# M4.net
KiCad netlist of a schematic drawn in Altium Designer
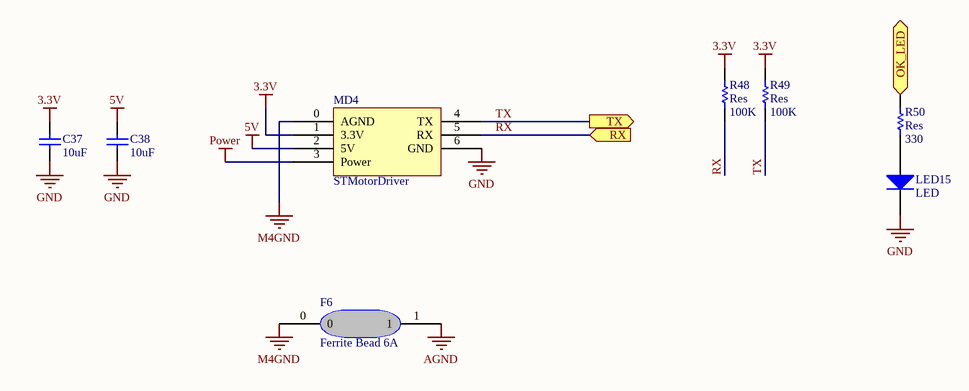
[diagram p0: M4.SchDoc]

(export (version "E")
  (design (tool "Eeschema 10.0.6"))
  (components
    (comp (ref "C37")
      (value "10uF")
      (footprint "2012[0805]")
      (description "Capacitor")
      (fields (field (name "Comment") "Cap_UP") (field (name "PUBLISHER") "Altium Limited"))
      (libsource (lib "KN2CLib") (part "Cap_UP"))
    )
    (comp (ref "C38")
      (value "10uF")
      (footprint "2012[0805]")
      (description "Capacitor")
      (fields (field (name "Comment") "Cap_UP") (field (name "PUBLISHER") "Altium Limited"))
      (libsource (lib "KN2CLib") (part "Cap_UP"))
    )
    (comp (ref "F6")
      (value "Ferrite Bead 6A")
      (footprint "f6A")
      (libsource (lib "Ferrite Bead") (part "F6A"))
    )
    (comp (ref "LED15")
      (value "LED")
      (footprint "2012[0805]")
      (description "1 Amp General Purpose Rectifier")
      (fields (field (name "PUBLISHER") "Altium Limited"))
      (libsource (lib "KN2CLib") (part "Diode"))
    )
    (comp (ref "MD4")
      (value "STMotorDriver")
      (footprint "MotorDriver")
      (libsource (lib "STMotorDriver") (part "STMotorDriver"))
    )
    (comp (ref "R48")
      (value "Res")
      (footprint "2012[0805]")
      (description "Semiconductor Resistor")
      (fields (field (name "ALTIUM_VALUE") "100K") (field (name "PUBLISHER") "Altium Limited"))
      (libsource (lib "KN2CLib") (part "Res"))
    )
    (comp (ref "R49")
      (value "Res")
      (footprint "2012[0805]")
      (description "Semiconductor Resistor")
      (fields (field (name "ALTIUM_VALUE") "100K") (field (name "PUBLISHER") "Altium Limited"))
      (libsource (lib "KN2CLib") (part "Res"))
    )
    (comp (ref "R50")
      (value "Res")
      (footprint "2012[0805]")
      (description "Semiconductor Resistor")
      (fields (field (name "ALTIUM_VALUE") "330") (field (name "PUBLISHER") "Altium Limited"))
      (libsource (lib "KN2CLib") (part "Res"))
    )
  )
  (nets
    (net (code "1") (name "/OK_LED") (class "Default")
      (node (ref "R50") (pin "1") (pinfunction "1_1") (pintype "passive"))
    )
    (net (code "2") (name "/RX") (class "Default")
      (node (ref "MD4") (pin "5") (pinfunction "RX_5") (pintype "passive"))
      (node (ref "R48") (pin "1") (pinfunction "1_1") (pintype "passive"))
    )
    (net (code "3") (name "/TX") (class "Default")
      (node (ref "MD4") (pin "4") (pinfunction "TX_4") (pintype "passive"))
      (node (ref "R49") (pin "1") (pinfunction "1_1") (pintype "passive"))
    )
    (net (code "4") (name "3.3V") (class "Default")
      (node (ref "C37") (pin "2") (pinfunction "2_2") (pintype "passive"))
      (node (ref "MD4") (pin "1") (pinfunction "3.3V_1") (pintype "passive"))
      (node (ref "R48") (pin "2") (pinfunction "2_2") (pintype "passive"))
      (node (ref "R49") (pin "2") (pinfunction "2_2") (pintype "passive"))
    )
    (net (code "5") (name "5V") (class "Default")
      (node (ref "C38") (pin "2") (pinfunction "2_2") (pintype "passive"))
      (node (ref "MD4") (pin "2") (pinfunction "5V_2") (pintype "passive"))
    )
    (net (code "6") (name "AGND") (class "Default")
      (node (ref "F6") (pin "1") (pinfunction "1_1") (pintype "passive"))
    )
    (net (code "7") (name "GND") (class "Default")
      (node (ref "C37") (pin "1") (pinfunction "1_1") (pintype "passive"))
      (node (ref "C38") (pin "1") (pinfunction "1_1") (pintype "passive"))
      (node (ref "LED15") (pin "2") (pinfunction "K_2") (pintype "passive"))
      (node (ref "MD4") (pin "6") (pinfunction "GND_6") (pintype "passive"))
    )
    (net (code "8") (name "M4GND") (class "Default")
      (node (ref "F6") (pin "0") (pinfunction "0_0") (pintype "passive"))
      (node (ref "MD4") (pin "0") (pinfunction "AGND_0") (pintype "passive"))
    )
    (net (code "9") (name "Net-(LED15-A)") (class "Default")
      (node (ref "LED15") (pin "1") (pinfunction "A_1") (pintype "passive"))
      (node (ref "R50") (pin "2") (pinfunction "2_2") (pintype "passive"))
    )
    (net (code "10") (name "Power") (class "Default")
      (node (ref "MD4") (pin "3") (pinfunction "Power_3") (pintype "passive"))
    )
  )
)
